# box.net
KiCad netlist of a schematic drawn in EAGLE
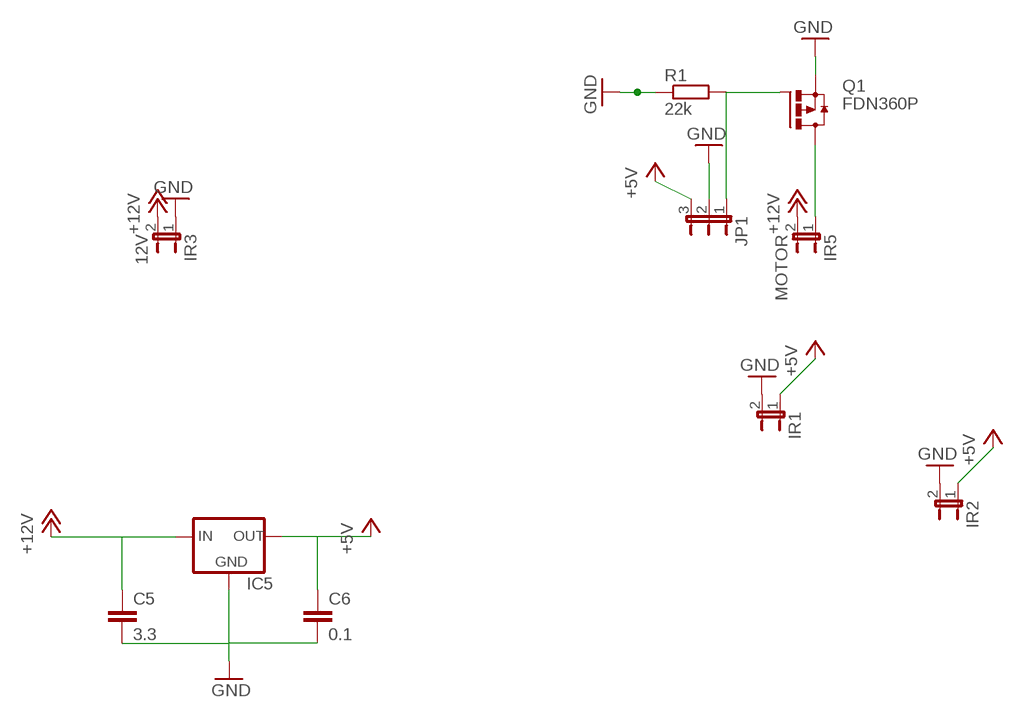
[diagram p0: schematic, sheet 1]

(export (version "E")
  (design (tool "Eeschema 10.0.6"))
  (components
    (comp (ref "C5")
      (value "3.3")
      (footprint "eagle-import:C025-024X044")
      (libsource (lib "eagle-import") (part "C-EU025-024X044"))
    )
    (comp (ref "C6")
      (value "0.1")
      (footprint "eagle-import:C025-024X044")
      (libsource (lib "eagle-import") (part "C-EU025-024X044"))
    )
    (comp (ref "IC5")
      (value "78XXL")
      (footprint "eagle-import:78XXL")
      (libsource (lib "eagle-import") (part "78XXL"))
    )
    (comp (ref "IR1")
      (value "JP1E")
      (footprint "eagle-import:JP1")
      (libsource (lib "eagle-import") (part "JP1E"))
    )
    (comp (ref "IR2")
      (value "JP1E")
      (footprint "eagle-import:JP1")
      (libsource (lib "eagle-import") (part "JP1E"))
    )
    (comp (ref "IR3")
      (value "12V")
      (footprint "eagle-import:JP1")
      (libsource (lib "eagle-import") (part "JP1E"))
    )
    (comp (ref "IR5")
      (value "MOTOR")
      (footprint "eagle-import:JP1")
      (libsource (lib "eagle-import") (part "JP1E"))
    )
    (comp (ref "JP1")
      (value "JP2E")
      (footprint "eagle-import:JP2")
      (libsource (lib "eagle-import") (part "JP2E"))
    )
    (comp (ref "Q1")
      (value "FDN360P")
      (footprint "eagle-import:SUPER-SOT3")
      (libsource (lib "eagle-import") (part "FDN360P"))
    )
    (comp (ref "R1")
      (value "22k")
      (footprint "eagle-import:0204_7")
      (libsource (lib "eagle-import") (part "R-EU_0204/7"))
    )
  )
  (nets
    (net (code "1") (name "+5V") (class "Default")
      (node (ref "C6") (pin "1") (pinfunction "1_1") (pintype "passive"))
      (node (ref "IC5") (pin "OUT") (pinfunction "OUT_OUT") (pintype "passive"))
      (node (ref "IR1") (pin "1") (pinfunction "1_1") (pintype "passive"))
      (node (ref "IR2") (pin "1") (pinfunction "1_1") (pintype "passive"))
      (node (ref "JP1") (pin "3") (pinfunction "3_3") (pintype "passive"))
    )
    (net (code "2") (name "+12V") (class "Default")
      (node (ref "C5") (pin "1") (pinfunction "1_1") (pintype "passive"))
      (node (ref "IC5") (pin "IN") (pinfunction "IN_IN") (pintype "input"))
      (node (ref "IR3") (pin "2") (pinfunction "2_2") (pintype "passive"))
      (node (ref "IR5") (pin "2") (pinfunction "2_2") (pintype "passive"))
    )
    (net (code "3") (name "GND") (class "Default")
      (node (ref "C5") (pin "2") (pinfunction "2_2") (pintype "passive"))
      (node (ref "C6") (pin "2") (pinfunction "2_2") (pintype "passive"))
      (node (ref "IC5") (pin "GND") (pinfunction "GND_GND") (pintype "input"))
      (node (ref "IR1") (pin "2") (pinfunction "2_2") (pintype "passive"))
      (node (ref "IR2") (pin "2") (pinfunction "2_2") (pintype "passive"))
      (node (ref "IR3") (pin "1") (pinfunction "1_1") (pintype "passive"))
      (node (ref "JP1") (pin "2") (pinfunction "2_2") (pintype "passive"))
      (node (ref "Q1") (pin "2") (pinfunction "S_2") (pintype "passive"))
      (node (ref "R1") (pin "1") (pinfunction "1_1") (pintype "passive"))
    )
    (net (code "4") (name "Net-(Q1-D)") (class "Default")
      (node (ref "IR5") (pin "1") (pinfunction "1_1") (pintype "passive"))
      (node (ref "Q1") (pin "3") (pinfunction "D_3") (pintype "passive"))
    )
    (net (code "5") (name "Net-(Q1-G)") (class "Default")
      (node (ref "JP1") (pin "1") (pinfunction "1_1") (pintype "passive"))
      (node (ref "Q1") (pin "1") (pinfunction "G_1") (pintype "passive"))
      (node (ref "R1") (pin "2") (pinfunction "2_2") (pintype "passive"))
    )
  )
)
